# CurrentSensorAC712-30.net
KiCad netlist of a schematic drawn in EAGLE
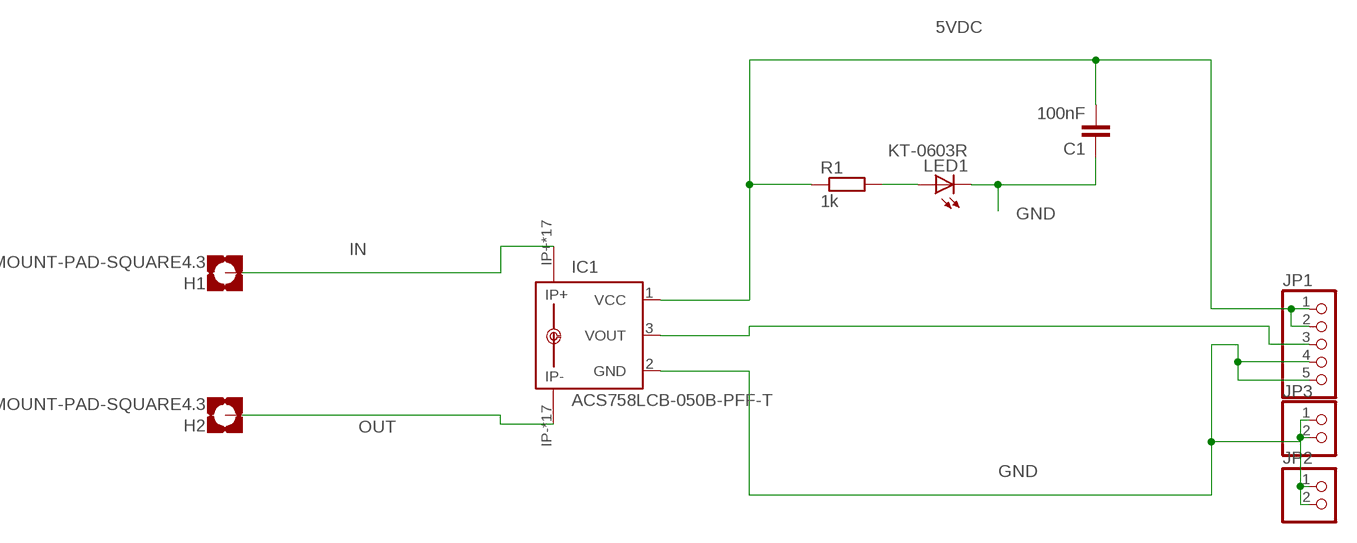
[diagram p0: schematic, sheet 1]

(export (version "E")
  (design (tool "Eeschema 10.0.6"))
  (components
    (comp (ref "C1")
      (value "100nF")
      (footprint "eagle-import:C0805")
      (libsource (lib "eagle-import") (part "C-EUC0805"))
    )
    (comp (ref "H1")
      (value "MOUNT-PAD-SQUARE4.3")
      (footprint "eagle-import:4,3-PAD-SQUARE")
      (libsource (lib "eagle-import") (part "MOUNT-PAD-SQUARE4.3"))
    )
    (comp (ref "H2")
      (value "MOUNT-PAD-SQUARE4.3")
      (footprint "eagle-import:4,3-PAD-SQUARE")
      (libsource (lib "eagle-import") (part "MOUNT-PAD-SQUARE4.3"))
    )
    (comp (ref "IC1")
      (value "ACS758LCB-050B-PFF-T")
      (footprint "eagle-import:CB-PFF")
      (libsource (lib "eagle-import") (part "ACS758LCB-050B-PFF-T"))
    )
    (comp (ref "JP1")
      (value "PINHD-1X5")
      (footprint "eagle-import:1X05")
      (libsource (lib "eagle-import") (part "PINHD-1X5"))
    )
    (comp (ref "JP2")
      (value "PINHD-1X2")
      (footprint "eagle-import:1X02")
      (libsource (lib "eagle-import") (part "PINHD-1X2"))
    )
    (comp (ref "JP3")
      (value "PINHD-1X2")
      (footprint "eagle-import:1X02")
      (libsource (lib "eagle-import") (part "PINHD-1X2"))
    )
    (comp (ref "LED1")
      (value "KT-0603R")
      (footprint "eagle-import:CHIPLED_0603")
      (libsource (lib "eagle-import") (part "LEDCHIPLED_0603"))
    )
    (comp (ref "R1")
      (value "1k")
      (footprint "eagle-import:R0805")
      (libsource (lib "eagle-import") (part "R-EU_R0805"))
    )
  )
  (nets
    (net (code "1") (name "/5VDC") (class "Default")
      (node (ref "C1") (pin "2") (pinfunction "2_2") (pintype "passive"))
      (node (ref "IC1") (pin "1") (pinfunction "VCC_1") (pintype "power_in"))
      (node (ref "JP1") (pin "1") (pinfunction "1_1") (pintype "passive"))
      (node (ref "JP1") (pin "2") (pinfunction "2_2") (pintype "passive"))
      (node (ref "R1") (pin "1") (pinfunction "1_1") (pintype "passive"))
    )
    (net (code "2") (name "/GND") (class "Default")
      (node (ref "C1") (pin "1") (pinfunction "1_1") (pintype "passive"))
      (node (ref "IC1") (pin "2") (pinfunction "GND_2") (pintype "power_in"))
      (node (ref "JP1") (pin "4") (pinfunction "4_4") (pintype "passive"))
      (node (ref "JP1") (pin "5") (pinfunction "5_5") (pintype "passive"))
      (node (ref "JP2") (pin "1") (pinfunction "1_1") (pintype "passive"))
      (node (ref "JP2") (pin "2") (pinfunction "2_2") (pintype "passive"))
      (node (ref "JP3") (pin "1") (pinfunction "1_1") (pintype "passive"))
      (node (ref "JP3") (pin "2") (pinfunction "2_2") (pintype "passive"))
      (node (ref "LED1") (pin "C") (pinfunction "C_C") (pintype "passive"))
    )
    (net (code "3") (name "/IN") (class "Default")
      (node (ref "H1") (pin "B4,3") (pinfunction "MOUNT_B4,3") (pintype "passive"))
      (node (ref "IC1") (pin "IP+") (pinfunction "IP+_IP+") (pintype "passive"))
      (node (ref "IC1") (pin "IP+@10") (pinfunction "IP+_IP+@10") (pintype "passive"))
      (node (ref "IC1") (pin "IP+@11") (pinfunction "IP+_IP+@11") (pintype "passive"))
      (node (ref "IC1") (pin "IP+@12") (pinfunction "IP+_IP+@12") (pintype "passive"))
      (node (ref "IC1") (pin "IP+@13") (pinfunction "IP+_IP+@13") (pintype "passive"))
      (node (ref "IC1") (pin "IP+@14") (pinfunction "IP+_IP+@14") (pintype "passive"))
      (node (ref "IC1") (pin "IP+@15") (pinfunction "IP+_IP+@15") (pintype "passive"))
      (node (ref "IC1") (pin "IP+@16") (pinfunction "IP+_IP+@16") (pintype "passive"))
      (node (ref "IC1") (pin "IP+@17") (pinfunction "IP+_IP+@17") (pintype "passive"))
      (node (ref "IC1") (pin "IP+@2") (pinfunction "IP+_IP+@2") (pintype "passive"))
      (node (ref "IC1") (pin "IP+@3") (pinfunction "IP+_IP+@3") (pintype "passive"))
      (node (ref "IC1") (pin "IP+@4") (pinfunction "IP+_IP+@4") (pintype "passive"))
      (node (ref "IC1") (pin "IP+@5") (pinfunction "IP+_IP+@5") (pintype "passive"))
      (node (ref "IC1") (pin "IP+@6") (pinfunction "IP+_IP+@6") (pintype "passive"))
      (node (ref "IC1") (pin "IP+@7") (pinfunction "IP+_IP+@7") (pintype "passive"))
      (node (ref "IC1") (pin "IP+@8") (pinfunction "IP+_IP+@8") (pintype "passive"))
      (node (ref "IC1") (pin "IP+@9") (pinfunction "IP+_IP+@9") (pintype "passive"))
    )
    (net (code "4") (name "/OUT") (class "Default")
      (node (ref "H2") (pin "B4,3") (pinfunction "MOUNT_B4,3") (pintype "passive"))
      (node (ref "IC1") (pin "IP-") (pinfunction "IP-_IP-") (pintype "passive"))
      (node (ref "IC1") (pin "IP-@10") (pinfunction "IP-_IP-@10") (pintype "passive"))
      (node (ref "IC1") (pin "IP-@11") (pinfunction "IP-_IP-@11") (pintype "passive"))
      (node (ref "IC1") (pin "IP-@12") (pinfunction "IP-_IP-@12") (pintype "passive"))
      (node (ref "IC1") (pin "IP-@13") (pinfunction "IP-_IP-@13") (pintype "passive"))
      (node (ref "IC1") (pin "IP-@14") (pinfunction "IP-_IP-@14") (pintype "passive"))
      (node (ref "IC1") (pin "IP-@15") (pinfunction "IP-_IP-@15") (pintype "passive"))
      (node (ref "IC1") (pin "IP-@16") (pinfunction "IP-_IP-@16") (pintype "passive"))
      (node (ref "IC1") (pin "IP-@17") (pinfunction "IP-_IP-@17") (pintype "passive"))
      (node (ref "IC1") (pin "IP-@2") (pinfunction "IP-_IP-@2") (pintype "passive"))
      (node (ref "IC1") (pin "IP-@3") (pinfunction "IP-_IP-@3") (pintype "passive"))
      (node (ref "IC1") (pin "IP-@4") (pinfunction "IP-_IP-@4") (pintype "passive"))
      (node (ref "IC1") (pin "IP-@5") (pinfunction "IP-_IP-@5") (pintype "passive"))
      (node (ref "IC1") (pin "IP-@6") (pinfunction "IP-_IP-@6") (pintype "passive"))
      (node (ref "IC1") (pin "IP-@7") (pinfunction "IP-_IP-@7") (pintype "passive"))
      (node (ref "IC1") (pin "IP-@8") (pinfunction "IP-_IP-@8") (pintype "passive"))
      (node (ref "IC1") (pin "IP-@9") (pinfunction "IP-_IP-@9") (pintype "passive"))
    )
    (net (code "5") (name "Net-(IC1-VOUT)") (class "Default")
      (node (ref "IC1") (pin "3") (pinfunction "VOUT_3") (pintype "output"))
      (node (ref "JP1") (pin "3") (pinfunction "3_3") (pintype "passive"))
    )
    (net (code "6") (name "Net-(LED1-PadA)") (class "Default")
      (node (ref "LED1") (pin "A") (pinfunction "A_A") (pintype "passive"))
      (node (ref "R1") (pin "2") (pinfunction "2_2") (pintype "passive"))
    )
  )
)
